# INNOVMED.net
KiCad netlist of a schematic drawn in Altium Designer
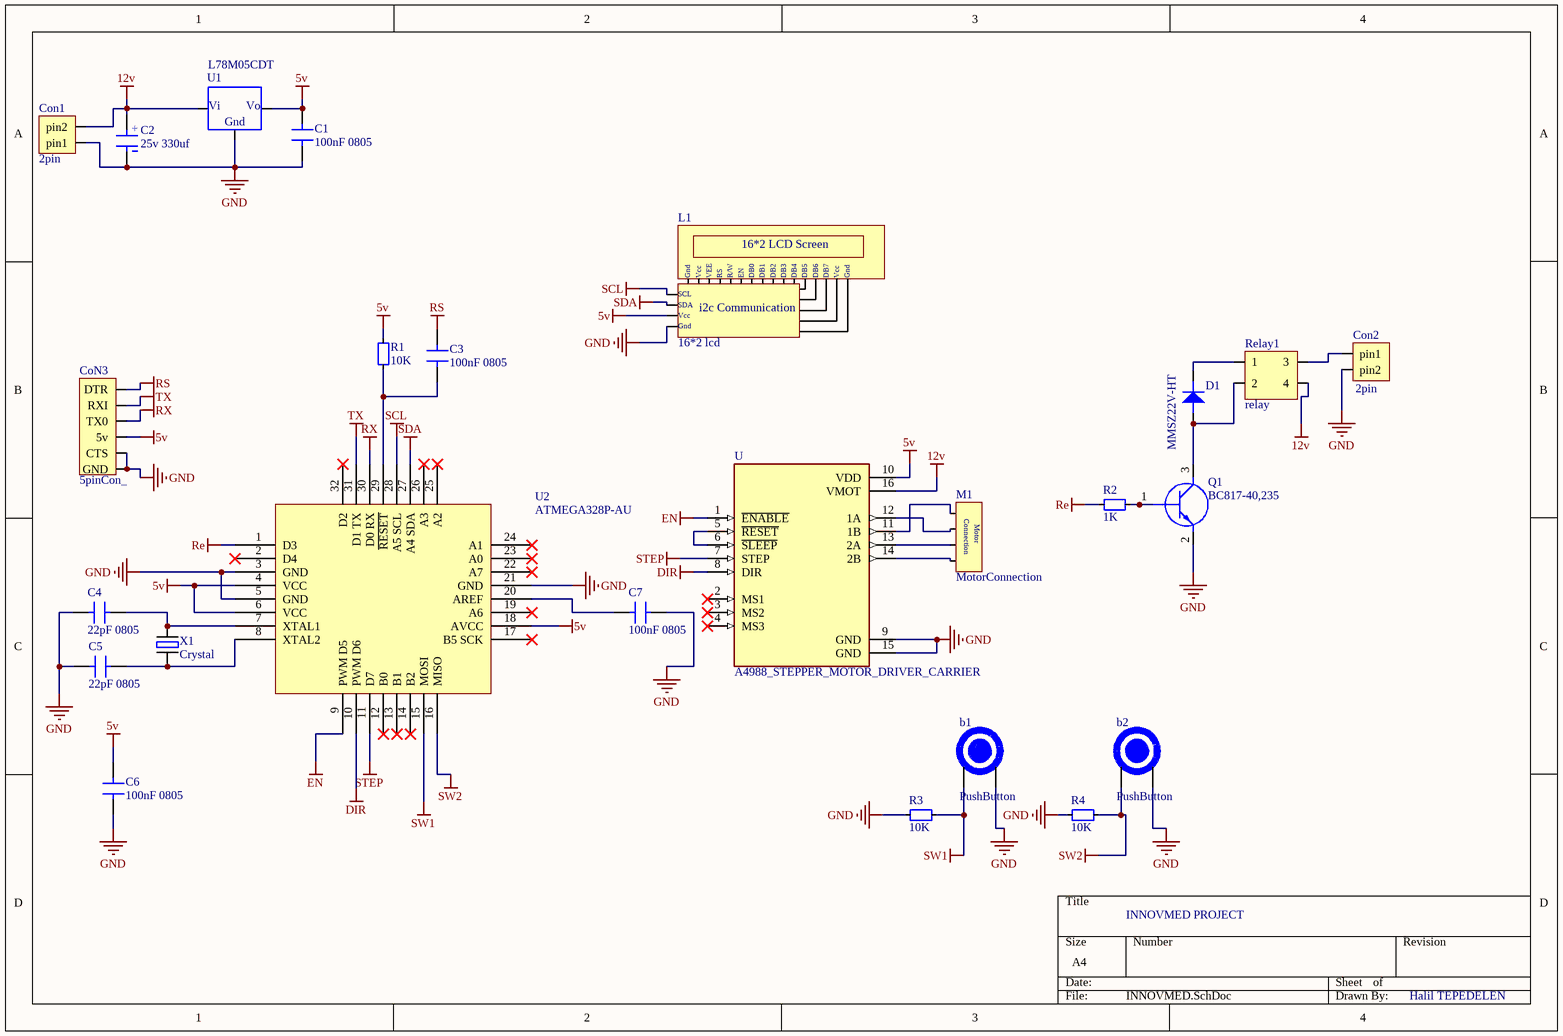
[diagram p0: INNOVMED.SchDoc]

(export (version "E")
  (design (tool "Eeschema 10.0.6"))
  (components
    (comp (ref "b1")
      (value "PushButton")
      (footprint "2pinCon")
      (libsource (lib "INNOVMED") (part "PushButton"))
    )
    (comp (ref "b2")
      (value "PushButton")
      (footprint "2pinCon")
      (libsource (lib "INNOVMED") (part "PushButton"))
    )
    (comp (ref "C1")
      (value "100nF 0805")
      (footprint "C-0805R")
      (fields
        (field (name "MANUFACTURER") "Nichicon")
        (field (name "MANUFACTURER PART NUMBER") "LKS1J472MESZ")
        (field (name "TOLERANCE") "20%")
      )
      (libsource (lib "INNOVMED") (part "100nF 0805"))
    )
    (comp (ref "C2")
      (value "25v 330uf")
      (footprint "10*10 capacitor")
      (libsource (lib "INNOVMED") (part "25v 330uf"))
    )
    (comp (ref "C3")
      (value "100nF 0805")
      (footprint "C-0805R")
      (fields
        (field (name "MANUFACTURER") "Nichicon")
        (field (name "MANUFACTURER PART NUMBER") "LKS1J472MESZ")
        (field (name "TOLERANCE") "20%")
      )
      (libsource (lib "INNOVMED") (part "100nF 0805"))
    )
    (comp (ref "C4")
      (value "22pF 0805")
      (footprint "C-0805R")
      (fields
        (field (name "MANUFACTURER") "Nichicon")
        (field (name "MANUFACTURER PART NUMBER") "LKS1J472MESZ")
        (field (name "TOLERANCE") "20%")
      )
      (libsource (lib "INNOVMED") (part "22pF 0805"))
    )
    (comp (ref "C5")
      (value "22pF 0805")
      (footprint "C-0805R")
      (fields
        (field (name "MANUFACTURER") "Nichicon")
        (field (name "MANUFACTURER PART NUMBER") "LKS1J472MESZ")
        (field (name "TOLERANCE") "20%")
      )
      (libsource (lib "INNOVMED") (part "22pF 0805"))
    )
    (comp (ref "C6")
      (value "100nF 0805")
      (footprint "C-0805R")
      (fields
        (field (name "MANUFACTURER") "Nichicon")
        (field (name "MANUFACTURER PART NUMBER") "LKS1J472MESZ")
        (field (name "TOLERANCE") "20%")
      )
      (libsource (lib "INNOVMED") (part "100nF 0805"))
    )
    (comp (ref "C7")
      (value "100nF 0805")
      (footprint "C-0805R")
      (fields
        (field (name "MANUFACTURER") "Nichicon")
        (field (name "MANUFACTURER PART NUMBER") "LKS1J472MESZ")
        (field (name "TOLERANCE") "20%")
      )
      (libsource (lib "INNOVMED") (part "100nF 0805"))
    )
    (comp (ref "Con1") (value "2pin") (footprint "Contactor") (libsource (lib "") (part "2pin_1")))
    (comp (ref "Con2") (value "2pin") (footprint "Contactor") (libsource (lib "INNOVMED") (part "2pin")))
    (comp (ref "CoN3")
      (value "5pinCon_")
      (footprint "5pinCon")
      (libsource (lib "INNOVMED") (part "5pinCon_"))
    )
    (comp (ref "D1")
      (value "MMSZ22V-HT")
      (footprint "SOD123")
      (libsource (lib "INNOVMED") (part "MMSZ22V-HT"))
    )
    (comp (ref "L1") (value "16*2 lcd") (footprint "4pinCon") (libsource (lib "INNOVMED") (part "16*2 lcd")))
    (comp (ref "M1")
      (value "MotorConnection")
      (footprint "4pinCon")
      (libsource (lib "INNOVMED") (part "MotorConnection"))
    )
    (comp (ref "Q1")
      (value "BC817-40,235")
      (footprint "SOT95P230X110-3N")
      (description "Transistor BJT NPN")
      (fields (field (name "MOUSER PART NUMBER") "771-BC817-40235") (field (name "RS PART NUMBER") "1707957"))
      (libsource (lib "INNOVMED") (part "BC817-40,235"))
    )
    (comp (ref "R1") (value "10K") (footprint "R-0805R") (libsource (lib "INNOVMED") (part "10K 0805")))
    (comp (ref "R2") (value "1K") (footprint "R-0805R") (libsource (lib "INNOVMED") (part "1K 0805")))
    (comp (ref "R3") (value "10K") (footprint "R-0805R") (libsource (lib "INNOVMED") (part "10K 0805")))
    (comp (ref "R4") (value "10K") (footprint "R-0805R") (libsource (lib "INNOVMED") (part "10K 0805")))
    (comp (ref "Relay1") (value "relay") (footprint "Relay") (libsource (lib "INNOVMED") (part "relay")))
    (comp (ref "U")
      (value "A4988_STEPPER_MOTOR_DRIVER_CARRIER")
      (footprint "MODULE_A4988_STEPPER_MOTOR_DRIVER_CARRIER")
      (description "Stepper Motor Driver")
      (fields (field (name "MP") "A4988 STEPPER MOTOR DRIVER CARRIER") (field (name "MF") "Pololu"))
      (libsource (lib "INNOVMED") (part "A4988_STEPPER_MOTOR_DRIVER_CARRIER"))
    )
    (comp (ref "U1")
      (value "L78M05CDT")
      (footprint "TO-252")
      (fields
        (field (name "MANUFACTURER") "STMicroelectronics")
        (field (name "MANUFACTURER PART NUMBER") "L78M15CDT")
      )
      (libsource (lib "INNOVMED") (part "L78M05"))
    )
    (comp (ref "U2")
      (value "ATMEGA328P-AU")
      (footprint "TQFP80P900X900X120-32N")
      (description "Microchip Technology ATMEGA328P-AN, 8bit AVR Microcontroller, 20MHz, 32 kB Flash, 32-Pin TQFP")
      (libsource (lib "INNOVMED") (part "ATMEGA328P-AU"))
    )
    (comp (ref "X1")
      (value "Crystal")
      (footprint "crystal")
      (description "AS49SD-16M-FC160F3-TR")
      (libsource (lib "INNOVMED") (part "Crystal"))
    )
  )
  (nets
    (net (code "1") (name "5v") (class "Default")
      (node (ref "C1") (pin "1") (pinfunction "1_1") (pintype "passive"))
      (node (ref "C6") (pin "1") (pinfunction "1_1") (pintype "passive"))
      (node (ref "CoN3") (pin "4") (pinfunction "5v_4") (pintype "passive"))
      (node (ref "L1") (pin "3") (pinfunction "3_3") (pintype "passive"))
      (node (ref "R1") (pin "2") (pinfunction "2_2") (pintype "passive"))
      (node (ref "U") (pin "10") (pinfunction "VDD_10") (pintype "power_in"))
      (node (ref "U1") (pin "2") (pinfunction "2_2") (pintype "passive"))
      (node (ref "U2") (pin "18") (pinfunction "AVCC_18") (pintype "passive"))
      (node (ref "U2") (pin "4") (pinfunction "VCC_4") (pintype "passive"))
      (node (ref "U2") (pin "6") (pinfunction "VCC_6") (pintype "passive"))
    )
    (net (code "2") (name "12v") (class "Default")
      (node (ref "C2") (pin "1") (pinfunction "1_1") (pintype "passive"))
      (node (ref "Con1") (pin "2") (pinfunction "pin2_2") (pintype "passive"))
      (node (ref "Relay1") (pin "4") (pinfunction "4_4") (pintype "passive"))
      (node (ref "U") (pin "16") (pinfunction "VMOT_16") (pintype "power_in"))
      (node (ref "U1") (pin "1") (pinfunction "1_1") (pintype "passive"))
    )
    (net (code "3") (name "DIR") (class "Default")
      (node (ref "U") (pin "8") (pinfunction "DIR_8") (pintype "input"))
      (node (ref "U2") (pin "10") (pinfunction "PWM_D6_10") (pintype "passive"))
    )
    (net (code "4") (name "EN") (class "Default")
      (node (ref "U") (pin "1") (pinfunction "~{ENABLE}_1") (pintype "input"))
      (node (ref "U2") (pin "9") (pinfunction "PWM_D5_9") (pintype "passive"))
    )
    (net (code "5") (name "GND") (class "Default")
      (node (ref "C1") (pin "2") (pinfunction "2_2") (pintype "passive"))
      (node (ref "C2") (pin "2") (pinfunction "2_2") (pintype "passive"))
      (node (ref "C4") (pin "2") (pinfunction "2_2") (pintype "passive"))
      (node (ref "C5") (pin "2") (pinfunction "2_2") (pintype "passive"))
      (node (ref "C6") (pin "2") (pinfunction "2_2") (pintype "passive"))
      (node (ref "C7") (pin "2") (pinfunction "2_2") (pintype "passive"))
      (node (ref "CoN3") (pin "5") (pinfunction "CTS_5") (pintype "passive"))
      (node (ref "CoN3") (pin "6") (pinfunction "GND_6") (pintype "passive"))
      (node (ref "Con1") (pin "1") (pinfunction "pin1_1") (pintype "passive"))
      (node (ref "Con2") (pin "2") (pinfunction "pin2_2") (pintype "passive"))
      (node (ref "L1") (pin "4") (pinfunction "4_4") (pintype "passive"))
      (node (ref "Q1") (pin "2") (pinfunction "E_2") (pintype "passive"))
      (node (ref "R3") (pin "1") (pinfunction "1_1") (pintype "passive"))
      (node (ref "R4") (pin "1") (pinfunction "1_1") (pintype "passive"))
      (node (ref "U") (pin "15") (pinfunction "GND_15") (pintype "power_in"))
      (node (ref "U") (pin "9") (pinfunction "GND_9") (pintype "power_in"))
      (node (ref "U1") (pin "3") (pinfunction "3_3") (pintype "passive"))
      (node (ref "U2") (pin "21") (pinfunction "GND_21") (pintype "passive"))
      (node (ref "U2") (pin "3") (pinfunction "GND_3") (pintype "passive"))
      (node (ref "U2") (pin "5") (pinfunction "GND_5") (pintype "passive"))
      (node (ref "b1") (pin "2") (pinfunction "2_2") (pintype "passive"))
      (node (ref "b2") (pin "2") (pinfunction "2_2") (pintype "passive"))
    )
    (net (code "6") (name "Net-(Con2-pin1)") (class "Default")
      (node (ref "Con2") (pin "1") (pinfunction "pin1_1") (pintype "passive"))
      (node (ref "Relay1") (pin "3") (pinfunction "3_3") (pintype "passive"))
    )
    (net (code "7") (name "Net-(D1-Padk)") (class "Default")
      (node (ref "D1") (pin "k") (pinfunction "k_k") (pintype "passive"))
      (node (ref "Relay1") (pin "1") (pinfunction "1_1") (pintype "passive"))
    )
    (net (code "8") (name "Net-(Q1-B)") (class "Default")
      (node (ref "Q1") (pin "1") (pinfunction "B_1") (pintype "passive"))
      (node (ref "R2") (pin "2") (pinfunction "2_2") (pintype "passive"))
    )
    (net (code "9") (name "Net-(Q1-C)") (class "Default")
      (node (ref "D1") (pin "a") (pinfunction "a_a") (pintype "passive"))
      (node (ref "Q1") (pin "3") (pinfunction "C_3") (pintype "passive"))
      (node (ref "Relay1") (pin "2") (pinfunction "2_2") (pintype "passive"))
    )
    (net (code "10") (name "Net-(U-1A)") (class "Default")
      (node (ref "M1") (pin "2") (pinfunction "2_2") (pintype "passive"))
      (node (ref "U") (pin "12") (pinfunction "1A_12") (pintype "output"))
    )
    (net (code "11") (name "Net-(U-1B)") (class "Default")
      (node (ref "M1") (pin "1") (pinfunction "1_1") (pintype "passive"))
      (node (ref "U") (pin "11") (pinfunction "1B_11") (pintype "output"))
    )
    (net (code "12") (name "Net-(U-2A)") (class "Default")
      (node (ref "M1") (pin "3") (pinfunction "3_3") (pintype "passive"))
      (node (ref "U") (pin "13") (pinfunction "2A_13") (pintype "output"))
    )
    (net (code "13") (name "Net-(U-2B)") (class "Default")
      (node (ref "M1") (pin "4") (pinfunction "4_4") (pintype "passive"))
      (node (ref "U") (pin "14") (pinfunction "2B_14") (pintype "output"))
    )
    (net (code "14") (name "Net-(U-~{RESET})") (class "Default")
      (node (ref "U") (pin "5") (pinfunction "~{RESET}_5") (pintype "input"))
      (node (ref "U") (pin "6") (pinfunction "~{SLEEP}_6") (pintype "input"))
    )
    (net (code "15") (name "Net-(U2-AREF)") (class "Default")
      (node (ref "C7") (pin "1") (pinfunction "1_1") (pintype "passive"))
      (node (ref "U2") (pin "20") (pinfunction "AREF_20") (pintype "passive"))
    )
    (net (code "16") (name "Net-(U2-XTAL1)") (class "Default")
      (node (ref "C4") (pin "1") (pinfunction "1_1") (pintype "passive"))
      (node (ref "U2") (pin "7") (pinfunction "XTAL1_7") (pintype "passive"))
      (node (ref "X1") (pin "1") (pinfunction "1_1") (pintype "passive"))
    )
    (net (code "17") (name "Net-(U2-XTAL2)") (class "Default")
      (node (ref "C5") (pin "1") (pinfunction "1_1") (pintype "passive"))
      (node (ref "U2") (pin "8") (pinfunction "XTAL2_8") (pintype "passive"))
      (node (ref "X1") (pin "2") (pinfunction "2_2") (pintype "passive"))
    )
    (net (code "18") (name "Net-(U2-~{RESET})") (class "Default")
      (node (ref "C3") (pin "2") (pinfunction "2_2") (pintype "passive"))
      (node (ref "R1") (pin "1") (pinfunction "1_1") (pintype "passive"))
      (node (ref "U2") (pin "29") (pinfunction "~{RESET}_29") (pintype "passive"))
    )
    (net (code "19") (name "RS") (class "Default")
      (node (ref "C3") (pin "1") (pinfunction "1_1") (pintype "passive"))
      (node (ref "CoN3") (pin "1") (pinfunction "DTR_1") (pintype "passive"))
    )
    (net (code "20") (name "RX") (class "Default")
      (node (ref "CoN3") (pin "3") (pinfunction "TX0_3") (pintype "passive"))
      (node (ref "U2") (pin "30") (pinfunction "D0_RX_30") (pintype "passive"))
    )
    (net (code "21") (name "Re") (class "Default")
      (node (ref "R2") (pin "1") (pinfunction "1_1") (pintype "passive"))
      (node (ref "U2") (pin "1") (pinfunction "D3_1") (pintype "passive"))
    )
    (net (code "22") (name "SCL") (class "Default")
      (node (ref "L1") (pin "1") (pinfunction "1_1") (pintype "passive"))
      (node (ref "U2") (pin "28") (pinfunction "A5_SCL_28") (pintype "passive"))
    )
    (net (code "23") (name "SDA") (class "Default")
      (node (ref "L1") (pin "2") (pinfunction "2_2") (pintype "passive"))
      (node (ref "U2") (pin "27") (pinfunction "A4_SDA_27") (pintype "passive"))
    )
    (net (code "24") (name "STEP") (class "Default")
      (node (ref "U") (pin "7") (pinfunction "STEP_7") (pintype "input"))
      (node (ref "U2") (pin "11") (pinfunction "D7_11") (pintype "passive"))
    )
    (net (code "25") (name "SW1") (class "Default")
      (node (ref "R3") (pin "2") (pinfunction "2_2") (pintype "passive"))
      (node (ref "U2") (pin "15") (pinfunction "MOSI_15") (pintype "passive"))
      (node (ref "b1") (pin "1") (pinfunction "1_1") (pintype "passive"))
    )
    (net (code "26") (name "SW2") (class "Default")
      (node (ref "R4") (pin "2") (pinfunction "2_2") (pintype "passive"))
      (node (ref "U2") (pin "16") (pinfunction "MISO_16") (pintype "passive"))
      (node (ref "b2") (pin "1") (pinfunction "1_1") (pintype "passive"))
    )
    (net (code "27") (name "TX") (class "Default")
      (node (ref "CoN3") (pin "2") (pinfunction "RXI_2") (pintype "passive"))
      (node (ref "U2") (pin "31") (pinfunction "D1_TX_31") (pintype "passive"))
    )
    (net (code "28") (name "unconnected-(U-MS1-Pad2)") (class "Default")
      (node (ref "U") (pin "2") (pinfunction "MS1_2") (pintype "input+no_connect"))
    )
    (net (code "29") (name "unconnected-(U-MS2-Pad3)") (class "Default")
      (node (ref "U") (pin "3") (pinfunction "MS2_3") (pintype "input+no_connect"))
    )
    (net (code "30") (name "unconnected-(U-MS3-Pad4)") (class "Default")
      (node (ref "U") (pin "4") (pinfunction "MS3_4") (pintype "input+no_connect"))
    )
    (net (code "31") (name "unconnected-(U2-A0-Pad23)") (class "Default")
      (node (ref "U2") (pin "23") (pinfunction "A0_23") (pintype "passive+no_connect"))
    )
    (net (code "32") (name "unconnected-(U2-A1-Pad24)") (class "Default")
      (node (ref "U2") (pin "24") (pinfunction "A1_24") (pintype "passive+no_connect"))
    )
    (net (code "33") (name "unconnected-(U2-A2-Pad25)") (class "Default")
      (node (ref "U2") (pin "25") (pinfunction "A2_25") (pintype "passive+no_connect"))
    )
    (net (code "34") (name "unconnected-(U2-A3-Pad26)") (class "Default")
      (node (ref "U2") (pin "26") (pinfunction "A3_26") (pintype "passive+no_connect"))
    )
    (net (code "35") (name "unconnected-(U2-A6-Pad19)") (class "Default")
      (node (ref "U2") (pin "19") (pinfunction "A6_19") (pintype "passive+no_connect"))
    )
    (net (code "36") (name "unconnected-(U2-A7-Pad22)") (class "Default")
      (node (ref "U2") (pin "22") (pinfunction "A7_22") (pintype "passive+no_connect"))
    )
    (net (code "37") (name "unconnected-(U2-B0-Pad12)") (class "Default")
      (node (ref "U2") (pin "12") (pinfunction "B0_12") (pintype "passive+no_connect"))
    )
    (net (code "38") (name "unconnected-(U2-B1-Pad13)") (class "Default")
      (node (ref "U2") (pin "13") (pinfunction "B1_13") (pintype "passive+no_connect"))
    )
    (net (code "39") (name "unconnected-(U2-B2-Pad14)") (class "Default")
      (node (ref "U2") (pin "14") (pinfunction "B2_14") (pintype "passive+no_connect"))
    )
    (net (code "40") (name "unconnected-(U2-B5_SCK-Pad17)") (class "Default")
      (node (ref "U2") (pin "17") (pinfunction "B5_SCK_17") (pintype "passive+no_connect"))
    )
    (net (code "41") (name "unconnected-(U2-D2-Pad32)") (class "Default")
      (node (ref "U2") (pin "32") (pinfunction "D2_32") (pintype "passive+no_connect"))
    )
    (net (code "42") (name "unconnected-(U2-D4-Pad2)") (class "Default")
      (node (ref "U2") (pin "2") (pinfunction "D4_2") (pintype "passive+no_connect"))
    )
  )
)
